# Controller.net
KiCad netlist of a schematic drawn in Altium Designer
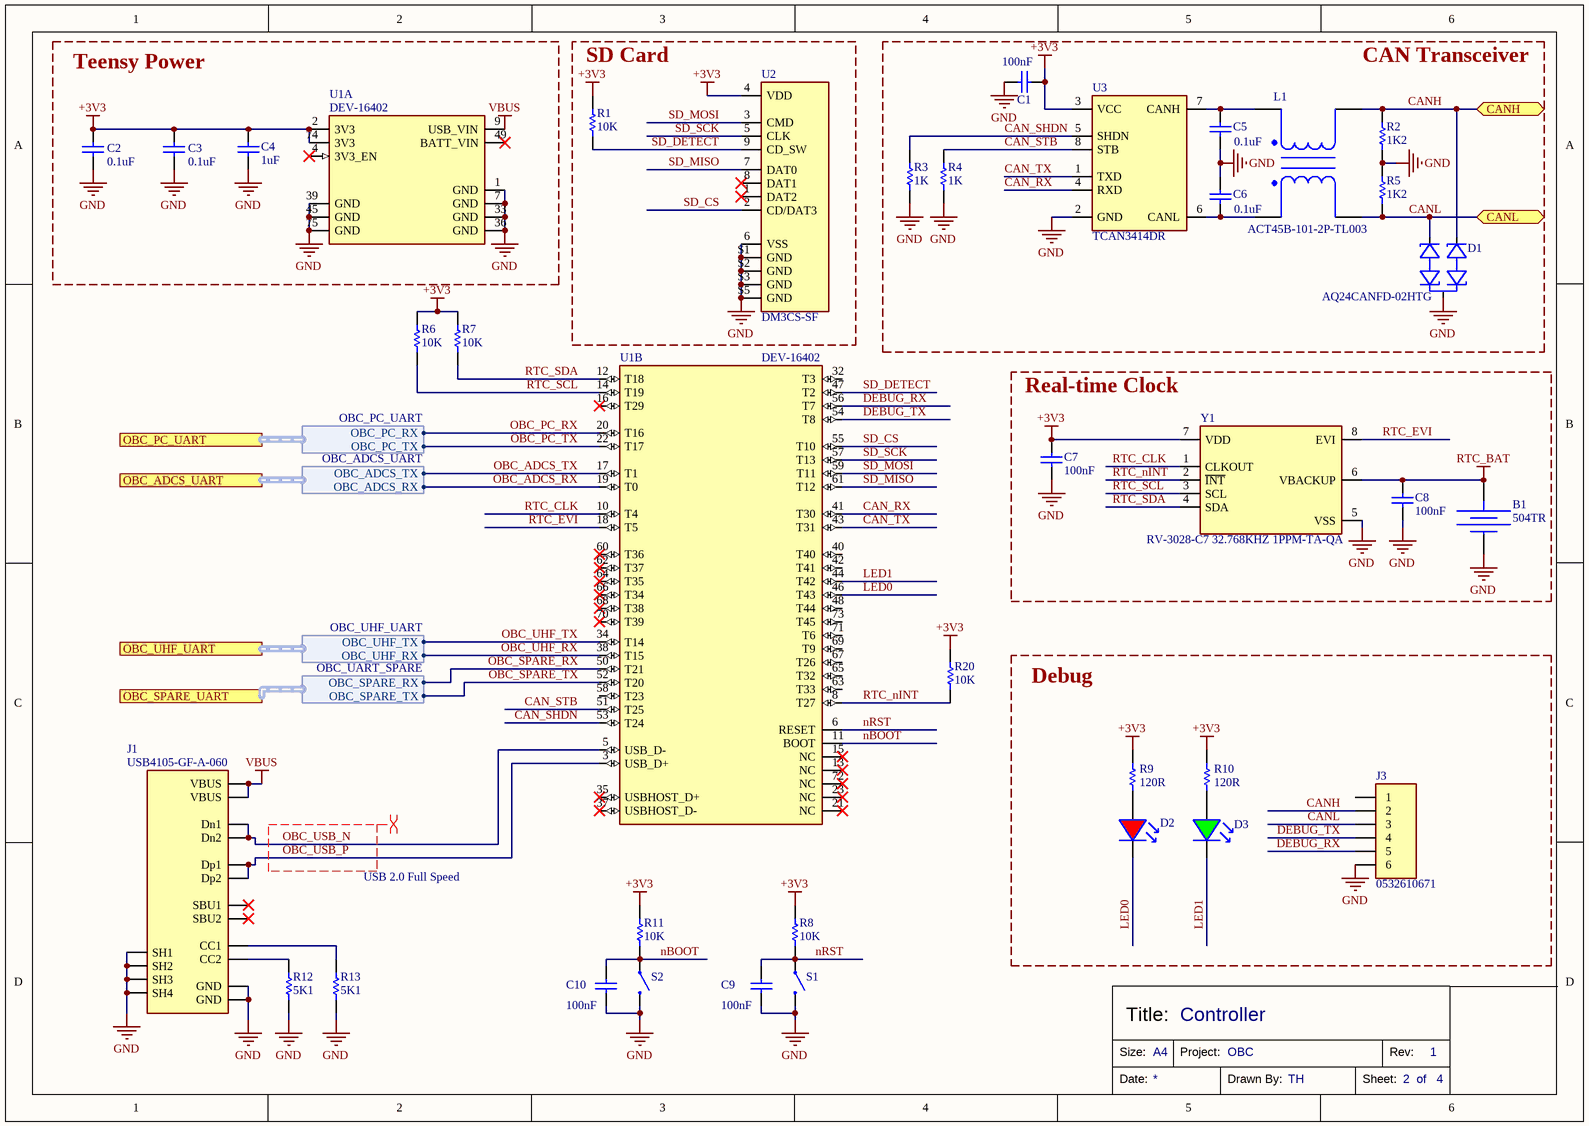
[diagram p0: Controller.SchDoc]

(export (version "E")
  (design (tool "Eeschema 10.0.6"))
  (components
    (comp (ref "B1")
      (value "504TR")
      (footprint "504TR")
      (description "Battery Holder (Open) Coin, 16.0mm 1 Cell SMD (SMT) Tab")
      (fields (field (name "DISTRIBUTOR PART NUMBER") "36-504CT-ND"))
      (libsource (lib "Ahristi_Library") (part "504TR"))
    )
    (comp (ref "C1")
      (value "C0603C104K5RACTU")
      (footprint "CAPC0603X040")
      (description "0.1 µF ±10% 50V Ceramic Capacitor X7R 0603 (1608 Metric)")
      (fields
        (field (name "TOLERANCE") "10%")
        (field (name "DISTRIBUTOR PART NUMBER") "399-C0603C104K5RACTUCT-ND")
        (field (name "CAPACITANCE") "100nF")
      )
      (libsource (lib "Ahristi_Library") (part "C0603C104K5RACTU"))
    )
    (comp (ref "C2")
      (value "CL05B104KB5NNNC")
      (footprint "CAPC0402X020")
      (description "0.1 µF ±10% 50V Ceramic Capacitor X7R 0402 (1005 Metric)")
      (fields
        (field (name "TOLERANCE") "10%")
        (field (name "DISTRIBUTOR PART NUMBER") "1276-CL05B104KB5NNNCCT-ND")
        (field (name "CAPACITANCE") "0.1uF")
      )
      (libsource (lib "Ahristi_Library") (part "CL05B104KB5NNNC"))
    )
    (comp (ref "C3")
      (value "CL05B104KB5NNNC")
      (footprint "CAPC0402X020")
      (description "0.1 µF ±10% 50V Ceramic Capacitor X7R 0402 (1005 Metric)")
      (fields
        (field (name "TOLERANCE") "10%")
        (field (name "DISTRIBUTOR PART NUMBER") "1276-CL05B104KB5NNNCCT-ND")
        (field (name "CAPACITANCE") "0.1uF")
      )
      (libsource (lib "Ahristi_Library") (part "CL05B104KB5NNNC"))
    )
    (comp (ref "C4")
      (value "CL21B105KAFNNNE")
      (footprint "CAPC0805X060")
      (description "1uF ±10% 25V Ceramic Capacitor X7R 0805 (2012 Metric)")
      (fields
        (field (name "DISTRIBUTOR PART NUMBER") "1276-1066-1-ND")
        (field (name "TOLERANCE") "10%")
        (field (name "CAPACITANCE") "1uF")
      )
      (libsource (lib "Ahristi_Library") (part "CL21B105KAFNNNE"))
    )
    (comp (ref "C5")
      (value "CL05B104KB5NNNC")
      (footprint "CAPC0402X020")
      (description "0.1 µF ±10% 50V Ceramic Capacitor X7R 0402 (1005 Metric)")
      (fields
        (field (name "TOLERANCE") "10%")
        (field (name "DISTRIBUTOR PART NUMBER") "1276-CL05B104KB5NNNCCT-ND")
        (field (name "CAPACITANCE") "0.1uF")
      )
      (libsource (lib "Ahristi_Library") (part "CL05B104KB5NNNC"))
    )
    (comp (ref "C6")
      (value "CL05B104KB5NNNC")
      (footprint "CAPC0402X020")
      (description "0.1 µF ±10% 50V Ceramic Capacitor X7R 0402 (1005 Metric)")
      (fields
        (field (name "TOLERANCE") "10%")
        (field (name "DISTRIBUTOR PART NUMBER") "1276-CL05B104KB5NNNCCT-ND")
        (field (name "CAPACITANCE") "0.1uF")
      )
      (libsource (lib "Ahristi_Library") (part "CL05B104KB5NNNC"))
    )
    (comp (ref "C7")
      (value "C0603C104K5RACTU")
      (footprint "CAPC0603X040")
      (description "0.1 µF ±10% 50V Ceramic Capacitor X7R 0603 (1608 Metric)")
      (fields
        (field (name "DISTRIBUTOR PART NUMBER") "399-C0603C104K5RACTUCT-ND")
        (field (name "TOLERANCE") "10%")
        (field (name "CAPACITANCE") "100nF")
      )
      (libsource (lib "Ahristi_Library") (part "C0603C104K5RACTU"))
    )
    (comp (ref "C8")
      (value "C0603C104K5RACTU")
      (footprint "CAPC0603X040")
      (description "0.1 µF ±10% 50V Ceramic Capacitor X7R 0603 (1608 Metric)")
      (fields
        (field (name "DISTRIBUTOR PART NUMBER") "399-C0603C104K5RACTUCT-ND")
        (field (name "TOLERANCE") "10%")
        (field (name "CAPACITANCE") "100nF")
      )
      (libsource (lib "Ahristi_Library") (part "C0603C104K5RACTU"))
    )
    (comp (ref "C9")
      (value "C0603C104K5RACTU")
      (footprint "CAPC0603X040")
      (description "0.1 µF ±10% 50V Ceramic Capacitor X7R 0603 (1608 Metric)")
      (fields
        (field (name "TOLERANCE") "10%")
        (field (name "DISTRIBUTOR PART NUMBER") "399-C0603C104K5RACTUCT-ND")
        (field (name "CAPACITANCE") "100nF")
      )
      (libsource (lib "Ahristi_Library") (part "C0603C104K5RACTU"))
    )
    (comp (ref "C10")
      (value "C0603C104K5RACTU")
      (footprint "CAPC0603X040")
      (description "0.1 µF ±10% 50V Ceramic Capacitor X7R 0603 (1608 Metric)")
      (fields
        (field (name "TOLERANCE") "10%")
        (field (name "DISTRIBUTOR PART NUMBER") "399-C0603C104K5RACTUCT-ND")
        (field (name "CAPACITANCE") "100nF")
      )
      (libsource (lib "Ahristi_Library") (part "C0603C104K5RACTU"))
    )
    (comp (ref "D1")
      (value "AQ24CANFD-02HTG")
      (footprint "SOT23-3 IC")
      (description "50V Clamp 3A (8/20µs) Ipp Tvs Diode Surface Mount SOT-23-3")
      (fields (field (name "DISTRIBUTOR PART NUMBER") "F10993CT-ND"))
      (libsource (lib "Ahristi_Library") (part "AQ24CANFD-02HTG"))
    )
    (comp (ref "D2")
      (value "LTST-C171KRKT")
      (footprint "LEDR_0805")
      (description "Red 631nm LED Indication - Discrete 2V 0805 (2012 Metric)")
      (fields (field (name "DISTRIBUTOR PART NUMBER") "160-1427-1-ND"))
      (libsource (lib "Ahristi_Library") (part "LTST-C171KRKT"))
    )
    (comp (ref "D3")
      (value "LTST-C171KGKT")
      (footprint "LEDG_0805")
      (description "LED Green 0805 00mW 120° 2.6V~3.1V 430mcd 513nm~528nm 525nm 5mA")
      (fields (field (name "DISTRIBUTOR PART NUMBER") "160-1426-1-ND"))
      (libsource (lib "Ahristi_Library") (part "KT-0805G"))
    )
    (comp (ref "J1")
      (value "USB4105-GF-A-060")
      (footprint "USB4105-GF-A-060")
      (fields (field (name "DISTRIBUTOR PART NUMBER") "2073-USB4105-GF-A-060CT-ND"))
      (libsource (lib "Ahristi_Library") (part "USB4105-GF-A-060"))
    )
    (comp (ref "J3")
      (value "0532610671")
      (footprint "0532610671")
      (description "Connector Header Surface Mount, Right Angle 6 position 0.049\" (1.25mm) Picoblade")
      (fields (field (name "DISTRIBUTOR PART NUMBER") "WM7624CT-ND"))
      (libsource (lib "Ahristi_Library") (part "0532610671"))
    )
    (comp (ref "L1")
      (value "ACT45B-101-2P-TL003")
      (footprint "ACT45B-101-2P-TL003")
      (description "Common Mode Choke 100 µH @ 100 kHz 2 Line Surface Mount 5.8 kOhms @ 10 MHz 150mA DCR 2Ohm")
      (fields (field (name "DISTRIBUTOR PART NUMBER") "445-3959-1-ND"))
      (libsource (lib "Ahristi_Library") (part "ACT45B-101-2P-TL003"))
    )
    (comp (ref "R1")
      (value "RMCF0805FT10K0")
      (footprint "RESC0805")
      (description "10 kOhms ±1% 0.125W, 1/8W Chip Resistor 0805 (2012 Metric) Automotive AEC-Q200 Thick Film")
      (fields
        (field (name "TOLERANCE") "1%")
        (field (name "DISTRIBUTOR PART NUMBER") "RMCF0805FT10K0CT-ND")
        (field (name "RESISTANCE") "10K")
      )
      (libsource (lib "Ahristi_Library") (part "RMCF0805FT10K0"))
    )
    (comp (ref "R2")
      (value "RMCF0603FT1K20")
      (footprint "RESC0603")
      (description "1.2 kOhms ±1% 0.1W, 1/10W Chip Resistor 0603 (1608 Metric) Automotive AEC-Q200 Thick Film")
      (fields
        (field (name "TOLERANCE") "1%")
        (field (name "DISTRIBUTOR PART NUMBER") "RMCF0603FT1K20CT-ND")
        (field (name "RESISTANCE") "1K2")
      )
      (libsource (lib "Ahristi_Library") (part "RMCF0603FT1K20"))
    )
    (comp (ref "R3")
      (value "RNCP0805FTD1K00")
      (footprint "RESC0805")
      (description "1 kOhms ±1% 0.25W, 1/4W Chip Resistor 0805 (2012 Metric) Anti-Sulfur Thin Film")
      (fields
        (field (name "TOLERANCE") "1%")
        (field (name "DISTRIBUTOR PART NUMBER") "RNCP0805FTD1K00CT-ND")
        (field (name "RESISTANCE") "1K")
      )
      (libsource (lib "Ahristi_Library") (part "RNCP0805FTD1K00"))
    )
    (comp (ref "R4")
      (value "RNCP0805FTD1K00")
      (footprint "RESC0805")
      (description "1 kOhms ±1% 0.25W, 1/4W Chip Resistor 0805 (2012 Metric) Anti-Sulfur Thin Film")
      (fields
        (field (name "TOLERANCE") "1%")
        (field (name "DISTRIBUTOR PART NUMBER") "RNCP0805FTD1K00CT-ND")
        (field (name "RESISTANCE") "1K")
      )
      (libsource (lib "Ahristi_Library") (part "RNCP0805FTD1K00"))
    )
    (comp (ref "R5")
      (value "RMCF0603FT1K20")
      (footprint "RESC0603")
      (description "1.2 kOhms ±1% 0.1W, 1/10W Chip Resistor 0603 (1608 Metric) Automotive AEC-Q200 Thick Film")
      (fields
        (field (name "TOLERANCE") "1%")
        (field (name "DISTRIBUTOR PART NUMBER") "RMCF0603FT1K20CT-ND")
        (field (name "RESISTANCE") "1K2")
      )
      (libsource (lib "Ahristi_Library") (part "RMCF0603FT1K20"))
    )
    (comp (ref "R6")
      (value "RMCF0603FT10K0")
      (footprint "RESC0603")
      (description "10 kOhms ±1% 0.1W, 1/10W Chip Resistor 0603 (1608 Metric) Automotive AEC-Q200 Thick Film")
      (fields
        (field (name "TOLERANCE") "1%")
        (field (name "DISTRIBUTOR PART NUMBER") "RMCF0603FT10K0CT-ND")
        (field (name "RESISTANCE") "10K")
      )
      (libsource (lib "Ahristi_Library") (part "RMCF0603FT10K0"))
    )
    (comp (ref "R7")
      (value "RMCF0603FT10K0")
      (footprint "RESC0603")
      (description "10 kOhms ±1% 0.1W, 1/10W Chip Resistor 0603 (1608 Metric) Automotive AEC-Q200 Thick Film")
      (fields
        (field (name "TOLERANCE") "1%")
        (field (name "DISTRIBUTOR PART NUMBER") "RMCF0603FT10K0CT-ND")
        (field (name "RESISTANCE") "10K")
      )
      (libsource (lib "Ahristi_Library") (part "RMCF0603FT10K0"))
    )
    (comp (ref "R8")
      (value "RMCF0805FT10K0")
      (footprint "RESC0805")
      (description "10 kOhms ±1% 0.125W, 1/8W Chip Resistor 0805 (2012 Metric) Automotive AEC-Q200 Thick Film")
      (fields
        (field (name "TOLERANCE") "1%")
        (field (name "DISTRIBUTOR PART NUMBER") "RMCF0805FT10K0CT-ND")
        (field (name "RESISTANCE") "10K")
      )
      (libsource (lib "Ahristi_Library") (part "RMCF0805FT10K0"))
    )
    (comp (ref "R9")
      (value "RMCF0805FT120R")
      (footprint "RESC0805")
      (description "120 Ohms ±1% 0.125W, 1/8W Chip Resistor 0805 (2012 Metric) Automotive AEC-Q200 Thick Film")
      (fields
        (field (name "TOLERANCE") "1%")
        (field (name "DISTRIBUTOR PART NUMBER") "738-RMCF0805FT120RCT-ND")
        (field (name "RESISTANCE") "120R")
      )
      (libsource (lib "Ahristi_Library") (part "RMCF0805FT120R"))
    )
    (comp (ref "R10")
      (value "RMCF0805FT120R")
      (footprint "RESC0805")
      (description "120 Ohms ±1% 0.125W, 1/8W Chip Resistor 0805 (2012 Metric) Automotive AEC-Q200 Thick Film")
      (fields
        (field (name "TOLERANCE") "1%")
        (field (name "DISTRIBUTOR PART NUMBER") "738-RMCF0805FT120RCT-ND")
        (field (name "RESISTANCE") "120R")
      )
      (libsource (lib "Ahristi_Library") (part "RMCF0805FT120R"))
    )
    (comp (ref "R11")
      (value "RMCF0805FT10K0")
      (footprint "RESC0805")
      (description "10 kOhms ±1% 0.125W, 1/8W Chip Resistor 0805 (2012 Metric) Automotive AEC-Q200 Thick Film")
      (fields
        (field (name "TOLERANCE") "1%")
        (field (name "DISTRIBUTOR PART NUMBER") "RMCF0805FT10K0CT-ND")
        (field (name "RESISTANCE") "10K")
      )
      (libsource (lib "Ahristi_Library") (part "RMCF0805FT10K0"))
    )
    (comp (ref "R12")
      (value "RMCF0603FT5K10")
      (footprint "RESC0603")
      (description "5.1 kOhms ±1% 0.1W, 1/10W Chip Resistor 0603 (1608 Metric) Automotive AEC-Q200 Thick Film")
      (fields
        (field (name "TOLERANCE") "1%")
        (field (name "DISTRIBUTOR PART NUMBER") "RMCF0603FT5K10CT-ND")
        (field (name "RESISTANCE") "5K1")
      )
      (libsource (lib "Ahristi_Library") (part "RMCF0603FT5K10"))
    )
    (comp (ref "R13")
      (value "RMCF0603FT5K10")
      (footprint "RESC0603")
      (description "5.1 kOhms ±1% 0.1W, 1/10W Chip Resistor 0603 (1608 Metric) Automotive AEC-Q200 Thick Film")
      (fields
        (field (name "TOLERANCE") "1%")
        (field (name "DISTRIBUTOR PART NUMBER") "RMCF0603FT5K10CT-ND")
        (field (name "RESISTANCE") "5K1")
      )
      (libsource (lib "Ahristi_Library") (part "RMCF0603FT5K10"))
    )
    (comp (ref "R20")
      (value "RMCF0603FT10K0")
      (footprint "RESC0603")
      (description "10 kOhms ±1% 0.1W, 1/10W Chip Resistor 0603 (1608 Metric) Automotive AEC-Q200 Thick Film")
      (fields
        (field (name "TOLERANCE") "1%")
        (field (name "DISTRIBUTOR PART NUMBER") "RMCF0603FT10K0CT-ND")
        (field (name "RESISTANCE") "10K")
      )
      (libsource (lib "Ahristi_Library") (part "RMCF0603FT10K0"))
    )
    (comp (ref "S1")
      (value "B3U-1000P")
      (footprint "B3U-1000P")
      (description "Tactile Switch SPST-NO Top Actuated Surface Mount")
      (fields (field (name "DISTRIBUTOR PART NUMBER") "SW1020CT-ND"))
      (libsource (lib "Ahristi_Library") (part "B3U-1000P"))
    )
    (comp (ref "S2")
      (value "B3U-1000P")
      (footprint "B3U-1000P")
      (description "Tactile Switch SPST-NO Top Actuated Surface Mount")
      (fields (field (name "DISTRIBUTOR PART NUMBER") "SW1020CT-ND"))
      (libsource (lib "Ahristi_Library") (part "B3U-1000P"))
    )
    (comp (ref "U1")
      (value "DEV-16402")
      (footprint "DEV-16402")
      (fields (field (name "DISTRIBUTOR PART NUMBER") "1568-16402-ND"))
      (libsource (lib "Ahristi_Library") (part "DEV-16402"))
    )
    (comp (ref "U2")
      (value "DM3CS-SF")
      (footprint "DM3CS-SF")
      (description "10 (8 + 2) Position Card Connector Secure Digital - microSD™ Surface Mount, Right Angle Gold")
      (fields (field (name "DISTRIBUTOR PART NUMBER") "HR1972CT-ND"))
      (libsource (lib "Ahristi_Library") (part "DM3CS-SF"))
    )
    (comp (ref "U3")
      (value "TCAN3414DR")
      (footprint "SOIC-8")
      (description "3.3 V CAN-FD transceiver, CAN/CAN-FD up to 8 Mb/s, ±58 V bus-fault tolerant, SOIC-8")
      (fields (field (name "DISTRIBUTOR PART NUMBER") "296-TCAN3414DRCT-ND"))
      (libsource (lib "Ahristi_Library") (part "TCAN3414DR"))
    )
    (comp (ref "Y1")
      (value "RV-3028-C7 32.768KHZ 1PPM-TA-QA")
      (footprint "RV-3028")
      (description "Real Time Clock (RTC) IC Clock/Calendar 2B, 43B I2C, 2-Wire Serial 8-WCDFN")
      (fields (field (name "DISTRIBUTOR PART NUMBER") "2195-RV-3028-C732.768KHZ1PPM-TA-QACT-ND"))
      (libsource (lib "Ahristi_Library") (part "RV-3028-C7 32.768KHZ 1PPM-TA-QA"))
    )
  )
  (nets
    (net (code "5") (name "+3V3") (class "Default")
      (node (ref "C1") (pin "2") (pinfunction "2_2") (pintype "passive"))
      (node (ref "C2") (pin "2") (pinfunction "2_2") (pintype "passive"))
      (node (ref "C3") (pin "2") (pinfunction "2_2") (pintype "passive"))
      (node (ref "C4") (pin "2") (pinfunction "2_2") (pintype "passive"))
      (node (ref "C7") (pin "2") (pinfunction "2_2") (pintype "passive"))
      (node (ref "R1") (pin "2") (pinfunction "2_2") (pintype "passive"))
      (node (ref "R10") (pin "2") (pinfunction "2_2") (pintype "passive"))
      (node (ref "R11") (pin "2") (pinfunction "2_2") (pintype "passive"))
      (node (ref "R20") (pin "2") (pinfunction "2_2") (pintype "passive"))
      (node (ref "R6") (pin "2") (pinfunction "2_2") (pintype "passive"))
      (node (ref "R7") (pin "2") (pinfunction "2_2") (pintype "passive"))
      (node (ref "R8") (pin "2") (pinfunction "2_2") (pintype "passive"))
      (node (ref "R9") (pin "2") (pinfunction "2_2") (pintype "passive"))
      (node (ref "U1") (pin "2") (pinfunction "3V3_2") (pintype "passive"))
      (node (ref "U1") (pin "74") (pinfunction "3V3_74") (pintype "passive"))
      (node (ref "U2") (pin "4") (pinfunction "VDD_4") (pintype "passive"))
      (node (ref "U3") (pin "3") (pinfunction "VCC_3") (pintype "passive"))
      (node (ref "Y1") (pin "7") (pinfunction "VDD_7") (pintype "passive"))
    )
    (net (code "6") (name "/CANH") (class "Default")
      (node (ref "D1") (pin "1") (pinfunction "1_1") (pintype "passive"))
      (node (ref "J3") (pin "2") (pinfunction "2_2") (pintype "passive"))
      (node (ref "L1") (pin "4") (pinfunction "4_4") (pintype "passive"))
      (node (ref "R2") (pin "2") (pinfunction "2_2") (pintype "passive"))
    )
    (net (code "7") (name "/CANL") (class "Default")
      (node (ref "D1") (pin "2") (pinfunction "2_2") (pintype "passive"))
      (node (ref "J3") (pin "3") (pinfunction "3_3") (pintype "passive"))
      (node (ref "L1") (pin "3") (pinfunction "3_3") (pintype "passive"))
      (node (ref "R5") (pin "1") (pinfunction "1_1") (pintype "passive"))
    )
    (net (code "8") (name "/CAN_RX") (class "Default")
      (node (ref "U1") (pin "41") (pinfunction "T30_41") (pintype "bidirectional"))
      (node (ref "U3") (pin "4") (pinfunction "RXD_4") (pintype "passive"))
    )
    (net (code "9") (name "/CAN_SHDN") (class "Default")
      (node (ref "R3") (pin "2") (pinfunction "2_2") (pintype "passive"))
      (node (ref "U1") (pin "53") (pinfunction "T24_53") (pintype "bidirectional"))
      (node (ref "U3") (pin "5") (pinfunction "SHDN_5") (pintype "passive"))
    )
    (net (code "10") (name "/CAN_STB") (class "Default")
      (node (ref "R4") (pin "2") (pinfunction "2_2") (pintype "passive"))
      (node (ref "U1") (pin "51") (pinfunction "T25_51") (pintype "bidirectional"))
      (node (ref "U3") (pin "8") (pinfunction "STB_8") (pintype "passive"))
    )
    (net (code "11") (name "/CAN_TX") (class "Default")
      (node (ref "U1") (pin "43") (pinfunction "T31_43") (pintype "bidirectional"))
      (node (ref "U3") (pin "1") (pinfunction "TXD_1") (pintype "passive"))
    )
    (net (code "12") (name "/DEBUG_RX") (class "Default")
      (node (ref "J3") (pin "5") (pinfunction "5_5") (pintype "passive"))
      (node (ref "U1") (pin "56") (pinfunction "T7_56") (pintype "bidirectional"))
    )
    (net (code "13") (name "/DEBUG_TX") (class "Default")
      (node (ref "J3") (pin "4") (pinfunction "4_4") (pintype "passive"))
      (node (ref "U1") (pin "54") (pinfunction "T8_54") (pintype "bidirectional"))
    )
    (net (code "14") (name "/LED0") (class "Default")
      (node (ref "D2") (pin "K") (pinfunction "K_K") (pintype "passive"))
      (node (ref "U1") (pin "46") (pinfunction "T43_46") (pintype "bidirectional"))
    )
    (net (code "15") (name "/LED1") (class "Default")
      (node (ref "D3") (pin "K") (pinfunction "K_K") (pintype "passive"))
      (node (ref "U1") (pin "44") (pinfunction "T42_44") (pintype "bidirectional"))
    )
    (net (code "16") (name "/OBC_ADCS_RX") (class "Default")
      (node (ref "U1") (pin "19") (pinfunction "T0_19") (pintype "bidirectional"))
    )
    (net (code "17") (name "/OBC_ADCS_TX") (class "Default")
      (node (ref "U1") (pin "17") (pinfunction "T1_17") (pintype "bidirectional"))
    )
    (net (code "18") (name "/OBC_PC_RX") (class "Default")
      (node (ref "U1") (pin "20") (pinfunction "T16_20") (pintype "bidirectional"))
    )
    (net (code "19") (name "/OBC_PC_TX") (class "Default")
      (node (ref "U1") (pin "22") (pinfunction "T17_22") (pintype "bidirectional"))
    )
    (net (code "20") (name "/OBC_SPARE_RX") (class "Default")
      (node (ref "U1") (pin "50") (pinfunction "T21_50") (pintype "bidirectional"))
    )
    (net (code "21") (name "/OBC_SPARE_TX") (class "Default")
      (node (ref "U1") (pin "52") (pinfunction "T20_52") (pintype "bidirectional"))
    )
    (net (code "22") (name "/OBC_UHF_RX") (class "Default")
      (node (ref "U1") (pin "38") (pinfunction "T15_38") (pintype "bidirectional"))
    )
    (net (code "23") (name "/OBC_UHF_TX") (class "Default")
      (node (ref "U1") (pin "34") (pinfunction "T14_34") (pintype "bidirectional"))
    )
    (net (code "24") (name "/OBC_USB_N") (class "Default")
      (node (ref "J1") (pin "A7") (pinfunction "Dn1_A7") (pintype "passive"))
      (node (ref "J1") (pin "B7") (pinfunction "Dn2_B7") (pintype "passive"))
      (node (ref "U1") (pin "5") (pinfunction "USB_D-_5") (pintype "bidirectional"))
    )
    (net (code "25") (name "/OBC_USB_P") (class "Default")
      (node (ref "J1") (pin "A6") (pinfunction "Dp1_A6") (pintype "passive"))
      (node (ref "J1") (pin "B6") (pinfunction "Dp2_B6") (pintype "passive"))
      (node (ref "U1") (pin "3") (pinfunction "USB_D+_3") (pintype "bidirectional"))
    )
    (net (code "26") (name "/RTC_CLK") (class "Default")
      (node (ref "U1") (pin "10") (pinfunction "T4_10") (pintype "bidirectional"))
      (node (ref "Y1") (pin "1") (pinfunction "CLKOUT_1") (pintype "passive"))
    )
    (net (code "27") (name "/RTC_EVI") (class "Default")
      (node (ref "U1") (pin "18") (pinfunction "T5_18") (pintype "bidirectional"))
      (node (ref "Y1") (pin "8") (pinfunction "EVI_8") (pintype "passive"))
    )
    (net (code "28") (name "/RTC_SCL") (class "Default")
      (node (ref "R6") (pin "1") (pinfunction "1_1") (pintype "passive"))
      (node (ref "U1") (pin "14") (pinfunction "T19_14") (pintype "bidirectional"))
      (node (ref "Y1") (pin "3") (pinfunction "SCL_3") (pintype "passive"))
    )
    (net (code "29") (name "/RTC_SDA") (class "Default")
      (node (ref "R7") (pin "1") (pinfunction "1_1") (pintype "passive"))
      (node (ref "U1") (pin "12") (pinfunction "T18_12") (pintype "bidirectional"))
      (node (ref "Y1") (pin "4") (pinfunction "SDA_4") (pintype "passive"))
    )
    (net (code "30") (name "/RTC_nINT") (class "Default")
      (node (ref "R20") (pin "1") (pinfunction "1_1") (pintype "passive"))
      (node (ref "U1") (pin "8") (pinfunction "T27_8") (pintype "bidirectional"))
      (node (ref "Y1") (pin "2") (pinfunction "~{INT}_2") (pintype "passive"))
    )
    (net (code "31") (name "/SD_CS") (class "Default")
      (node (ref "U1") (pin "55") (pinfunction "T10_55") (pintype "bidirectional"))
      (node (ref "U2") (pin "2") (pinfunction "CD/DAT3_2") (pintype "passive"))
    )
    (net (code "32") (name "/SD_DETECT") (class "Default")
      (node (ref "R1") (pin "1") (pinfunction "1_1") (pintype "passive"))
      (node (ref "U1") (pin "47") (pinfunction "T2_47") (pintype "bidirectional"))
      (node (ref "U2") (pin "9") (pinfunction "CD_SW_9") (pintype "passive"))
    )
    (net (code "33") (name "/SD_MISO") (class "Default")
      (node (ref "U1") (pin "61") (pinfunction "T12_61") (pintype "bidirectional"))
      (node (ref "U2") (pin "7") (pinfunction "DAT0_7") (pintype "passive"))
    )
    (net (code "34") (name "/SD_MOSI") (class "Default")
      (node (ref "U1") (pin "59") (pinfunction "T11_59") (pintype "bidirectional"))
      (node (ref "U2") (pin "3") (pinfunction "CMD_3") (pintype "passive"))
    )
    (net (code "35") (name "/SD_SCK") (class "Default")
      (node (ref "U1") (pin "57") (pinfunction "T13_57") (pintype "bidirectional"))
      (node (ref "U2") (pin "5") (pinfunction "CLK_5") (pintype "passive"))
    )
    (net (code "36") (name "/nBOOT") (class "Default")
      (node (ref "C10") (pin "2") (pinfunction "2_2") (pintype "passive"))
      (node (ref "R11") (pin "1") (pinfunction "1_1") (pintype "passive"))
      (node (ref "S2") (pin "1") (pinfunction "1_1") (pintype "passive"))
      (node (ref "U1") (pin "11") (pinfunction "BOOT_11") (pintype "open_collector"))
    )
    (net (code "37") (name "/nRST") (class "Default")
      (node (ref "C9") (pin "2") (pinfunction "2_2") (pintype "passive"))
      (node (ref "R8") (pin "1") (pinfunction "1_1") (pintype "passive"))
      (node (ref "S1") (pin "1") (pinfunction "1_1") (pintype "passive"))
      (node (ref "U1") (pin "6") (pinfunction "RESET_6") (pintype "open_collector"))
    )
    (net (code "42") (name "GND") (class "Default")
      (node (ref "B1") (pin "2") (pinfunction "2_2") (pintype "passive"))
      (node (ref "C1") (pin "1") (pinfunction "1_1") (pintype "passive"))
      (node (ref "C10") (pin "1") (pinfunction "1_1") (pintype "passive"))
      (node (ref "C2") (pin "1") (pinfunction "1_1") (pintype "passive"))
      (node (ref "C3") (pin "1") (pinfunction "1_1") (pintype "passive"))
      (node (ref "C4") (pin "1") (pinfunction "1_1") (pintype "passive"))
      (node (ref "C5") (pin "1") (pinfunction "1_1") (pintype "passive"))
      (node (ref "C6") (pin "2") (pinfunction "2_2") (pintype "passive"))
      (node (ref "C7") (pin "1") (pinfunction "1_1") (pintype "passive"))
      (node (ref "C8") (pin "1") (pinfunction "1_1") (pintype "passive"))
      (node (ref "C9") (pin "1") (pinfunction "1_1") (pintype "passive"))
      (node (ref "D1") (pin "3") (pinfunction "3_3") (pintype "passive"))
      (node (ref "J1") (pin "A1_B12") (pinfunction "GND_A1_B12") (pintype "passive"))
      (node (ref "J1") (pin "B1_A12") (pinfunction "GND_B1_A12") (pintype "passive"))
      (node (ref "J1") (pin "SH1") (pinfunction "SH1_SH1") (pintype "passive"))
      (node (ref "J1") (pin "SH2") (pinfunction "SH2_SH2") (pintype "passive"))
      (node (ref "J1") (pin "SH3") (pinfunction "SH3_SH3") (pintype "passive"))
      (node (ref "J1") (pin "SH4") (pinfunction "SH4_SH4") (pintype "passive"))
      (node (ref "J3") (pin "6") (pinfunction "6_6") (pintype "passive"))
      (node (ref "R12") (pin "1") (pinfunction "1_1") (pintype "passive"))
      (node (ref "R13") (pin "1") (pinfunction "1_1") (pintype "passive"))
      (node (ref "R2") (pin "1") (pinfunction "1_1") (pintype "passive"))
      (node (ref "R3") (pin "1") (pinfunction "1_1") (pintype "passive"))
      (node (ref "R4") (pin "1") (pinfunction "1_1") (pintype "passive"))
      (node (ref "R5") (pin "2") (pinfunction "2_2") (pintype "passive"))
      (node (ref "S1") (pin "2") (pinfunction "2_2") (pintype "passive"))
      (node (ref "S2") (pin "2") (pinfunction "2_2") (pintype "passive"))
      (node (ref "U1") (pin "1") (pinfunction "GND_1") (pintype "passive"))
      (node (ref "U1") (pin "33") (pinfunction "GND_33") (pintype "passive"))
      (node (ref "U1") (pin "36") (pinfunction "GND_36") (pintype "passive"))
      (node (ref "U1") (pin "39") (pinfunction "GND_39") (pintype "passive"))
      (node (ref "U1") (pin "45") (pinfunction "GND_45") (pintype "passive"))
      (node (ref "U1") (pin "7") (pinfunction "GND_7") (pintype "open_collector"))
      (node (ref "U1") (pin "75") (pinfunction "GND_75") (pintype "passive"))
      (node (ref "U2") (pin "6") (pinfunction "VSS_6") (pintype "passive"))
      (node (ref "U2") (pin "S1") (pinfunction "GND_S1") (pintype "passive"))
      (node (ref "U2") (pin "S2") (pinfunction "GND_S2") (pintype "passive"))
      (node (ref "U2") (pin "S3") (pinfunction "GND_S3") (pintype "passive"))
      (node (ref "U2") (pin "S5") (pinfunction "GND_S5") (pintype "passive"))
      (node (ref "U3") (pin "2") (pinfunction "GND_2") (pintype "passive"))
      (node (ref "Y1") (pin "5") (pinfunction "VSS_5") (pintype "passive"))
    )
    (net (code "43") (name "Net-(D2-PadA)") (class "Default")
      (node (ref "D2") (pin "A") (pinfunction "A_A") (pintype "passive"))
      (node (ref "R9") (pin "1") (pinfunction "1_1") (pintype "passive"))
    )
    (net (code "44") (name "Net-(D3-PadA)") (class "Default")
      (node (ref "D3") (pin "A") (pinfunction "A_A") (pintype "passive"))
      (node (ref "R10") (pin "1") (pinfunction "1_1") (pintype "passive"))
    )
    (net (code "45") (name "Net-(J1-CC1)") (class "Default")
      (node (ref "J1") (pin "A5") (pinfunction "CC1_A5") (pintype "passive"))
      (node (ref "R13") (pin "2") (pinfunction "2_2") (pintype "passive"))
    )
    (net (code "46") (name "Net-(J1-CC2)") (class "Default")
      (node (ref "J1") (pin "B5") (pinfunction "CC2_B5") (pintype "passive"))
      (node (ref "R12") (pin "2") (pinfunction "2_2") (pintype "passive"))
    )
    (net (code "47") (name "Net-(U3-CANH)") (class "Default")
      (node (ref "C5") (pin "2") (pinfunction "2_2") (pintype "passive"))
      (node (ref "L1") (pin "1") (pinfunction "1_1") (pintype "passive"))
      (node (ref "U3") (pin "7") (pinfunction "CANH_7") (pintype "passive"))
    )
    (net (code "48") (name "Net-(U3-CANL)") (class "Default")
      (node (ref "C6") (pin "1") (pinfunction "1_1") (pintype "passive"))
      (node (ref "L1") (pin "2") (pinfunction "2_2") (pintype "passive"))
      (node (ref "U3") (pin "6") (pinfunction "CANL_6") (pintype "passive"))
    )
    (net (code "49") (name "RTC_BAT") (class "Default")
      (node (ref "B1") (pin "1") (pinfunction "1_1") (pintype "passive"))
      (node (ref "C8") (pin "2") (pinfunction "2_2") (pintype "passive"))
      (node (ref "Y1") (pin "6") (pinfunction "VBACKUP_6") (pintype "passive"))
    )
    (net (code "50") (name "VBUS") (class "Default")
      (node (ref "J1") (pin "A4_B9") (pinfunction "VBUS_A4_B9") (pintype "passive"))
      (node (ref "J1") (pin "B4_A9") (pinfunction "VBUS_B4_A9") (pintype "passive"))
      (node (ref "U1") (pin "9") (pinfunction "USB_VIN_9") (pintype "passive"))
    )
    (net (code "51") (name "unconnected-(J1-SBU1-PadA8)") (class "Default")
      (node (ref "J1") (pin "A8") (pinfunction "SBU1_A8") (pintype "passive+no_connect"))
    )
    (net (code "52") (name "unconnected-(J1-SBU2-PadB8)") (class "Default")
      (node (ref "J1") (pin "B8") (pinfunction "SBU2_B8") (pintype "passive+no_connect"))
    )
    (net (code "53") (name "unconnected-(J3-Pad1)") (class "Default")
      (node (ref "J3") (pin "1") (pinfunction "1_1") (pintype "passive"))
    )
    (net (code "54") (name "unconnected-(U1A-3V3_EN-Pad4)") (class "Default")
      (node (ref "U1") (pin "4") (pinfunction "3V3_EN_4") (pintype "input+no_connect"))
    )
    (net (code "55") (name "unconnected-(U1A-BATT_VIN-Pad49)") (class "Default")
      (node (ref "U1") (pin "49") (pinfunction "BATT_VIN_49") (pintype "passive+no_connect"))
    )
    (net (code "56") (name "unconnected-(U1B-NC-Pad13)") (class "Default")
      (node (ref "U1") (pin "13") (pinfunction "NC_13") (pintype "passive+no_connect"))
    )
    (net (code "57") (name "unconnected-(U1B-NC-Pad15)") (class "Default")
      (node (ref "U1") (pin "15") (pinfunction "NC_15") (pintype "passive+no_connect"))
    )
    (net (code "58") (name "unconnected-(U1B-NC-Pad21)") (class "Default")
      (node (ref "U1") (pin "21") (pinfunction "NC_21") (pintype "passive+no_connect"))
    )
    (net (code "59") (name "unconnected-(U1B-NC-Pad23)") (class "Default")
      (node (ref "U1") (pin "23") (pinfunction "NC_23") (pintype "passive+no_connect"))
    )
    (net (code "60") (name "unconnected-(U1B-NC-Pad72)") (class "Default")
      (node (ref "U1") (pin "72") (pinfunction "NC_72") (pintype "passive+no_connect"))
    )
    (net (code "61") (name "unconnected-(U1B-T3-Pad32)") (class "Default")
      (node (ref "U1") (pin "32") (pinfunction "T3_32") (pintype "bidirectional"))
    )
    (net (code "62") (name "unconnected-(U1B-T6-Pad71)") (class "Default")
      (node (ref "U1") (pin "71") (pinfunction "T6_71") (pintype "bidirectional"))
    )
    (net (code "63") (name "unconnected-(U1B-T9-Pad69)") (class "Default")
      (node (ref "U1") (pin "69") (pinfunction "T9_69") (pintype "bidirectional"))
    )
    (net (code "64") (name "unconnected-(U1B-T23-Pad58)") (class "Default")
      (node (ref "U1") (pin "58") (pinfunction "T23_58") (pintype "bidirectional"))
    )
    (net (code "65") (name "unconnected-(U1B-T26-Pad67)") (class "Default")
      (node (ref "U1") (pin "67") (pinfunction "T26_67") (pintype "bidirectional"))
    )
    (net (code "66") (name "unconnected-(U1B-T29-Pad16)") (class "Default")
      (node (ref "U1") (pin "16") (pinfunction "T29_16") (pintype "bidirectional+no_connect"))
    )
    (net (code "67") (name "unconnected-(U1B-T32-Pad65)") (class "Default")
      (node (ref "U1") (pin "65") (pinfunction "T32_65") (pintype "bidirectional"))
    )
    (net (code "68") (name "unconnected-(U1B-T33-Pad63)") (class "Default")
      (node (ref "U1") (pin "63") (pinfunction "T33_63") (pintype "bidirectional"))
    )
    (net (code "69") (name "unconnected-(U1B-T34-Pad66)") (class "Default")
      (node (ref "U1") (pin "66") (pinfunction "T34_66") (pintype "bidirectional+no_connect"))
    )
    (net (code "70") (name "unconnected-(U1B-T35-Pad64)") (class "Default")
      (node (ref "U1") (pin "64") (pinfunction "T35_64") (pintype "bidirectional+no_connect"))
    )
    (net (code "71") (name "unconnected-(U1B-T36-Pad60)") (class "Default")
      (node (ref "U1") (pin "60") (pinfunction "T36_60") (pintype "bidirectional+no_connect"))
    )
    (net (code "72") (name "unconnected-(U1B-T37-Pad62)") (class "Default")
      (node (ref "U1") (pin "62") (pinfunction "T37_62") (pintype "bidirectional+no_connect"))
    )
    (net (code "73") (name "unconnected-(U1B-T38-Pad68)") (class "Default")
      (node (ref "U1") (pin "68") (pinfunction "T38_68") (pintype "bidirectional+no_connect"))
    )
    (net (code "74") (name "unconnected-(U1B-T39-Pad70)") (class "Default")
      (node (ref "U1") (pin "70") (pinfunction "T39_70") (pintype "bidirectional+no_connect"))
    )
    (net (code "75") (name "unconnected-(U1B-T40-Pad40)") (class "Default")
      (node (ref "U1") (pin "40") (pinfunction "T40_40") (pintype "bidirectional"))
    )
    (net (code "76") (name "unconnected-(U1B-T41-Pad42)") (class "Default")
      (node (ref "U1") (pin "42") (pinfunction "T41_42") (pintype "bidirectional"))
    )
    (net (code "77") (name "unconnected-(U1B-T44-Pad48)") (class "Default")
      (node (ref "U1") (pin "48") (pinfunction "T44_48") (pintype "bidirectional"))
    )
    (net (code "78") (name "unconnected-(U1B-T45-Pad73)") (class "Default")
      (node (ref "U1") (pin "73") (pinfunction "T45_73") (pintype "bidirectional"))
    )
    (net (code "79") (name "unconnected-(U1B-USBHOST_D+-Pad35)") (class "Default")
      (node (ref "U1") (pin "35") (pinfunction "USBHOST_D+_35") (pintype "bidirectional+no_connect"))
    )
    (net (code "80") (name "unconnected-(U1B-USBHOST_D--Pad37)") (class "Default")
      (node (ref "U1") (pin "37") (pinfunction "USBHOST_D-_37") (pintype "bidirectional+no_connect"))
    )
    (net (code "81") (name "unconnected-(U2-DAT1-Pad8)") (class "Default")
      (node (ref "U2") (pin "8") (pinfunction "DAT1_8") (pintype "passive+no_connect"))
    )
    (net (code "82") (name "unconnected-(U2-DAT2-Pad1)") (class "Default")
      (node (ref "U2") (pin "1") (pinfunction "DAT2_1") (pintype "passive+no_connect"))
    )
  )
)
